# USB_Power.net
KiCad netlist of a schematic drawn in Altium Designer
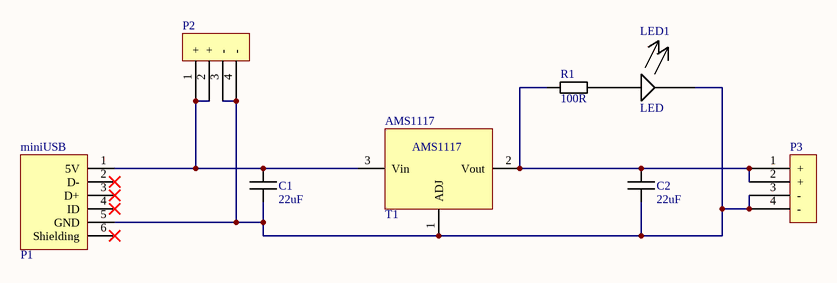
[diagram p0: USB Power.SchDoc]

(export (version "E")
  (design (tool "Eeschema 10.0.6"))
  (components
    (comp (ref "AMS1117")
      (value "T1")
      (footprint "SOT-223")
      (libsource (lib "AMS1117 breakout") (part "AMS1117"))
    )
    (comp (ref "C1")
      (value "22uF")
      (footprint "0805-C")
      (libsource (lib "AMS1117 breakout") (part "Capacitor"))
    )
    (comp (ref "C2")
      (value "22uF")
      (footprint "0805-C")
      (libsource (lib "AMS1117 breakout") (part "Capacitor"))
    )
    (comp (ref "LED1") (value "LED") (footprint "LED 3mm") (libsource (lib "LEDs") (part "LED")))
    (comp (ref "miniUSB")
      (value "P1")
      (footprint "miniUSB")
      (libsource (lib "AMS1117 breakout") (part "miniUSB"))
    )
    (comp (ref "P2")
      (value "Header 1x4 ++--")
      (footprint "Header 4x1 long")
      (libsource (lib "") (part "Header 1x4 ++--_1"))
    )
    (comp (ref "P3")
      (value "Header 1x4 ++--")
      (footprint "Header 4x1 long")
      (libsource (lib "Headers") (part "Header 1x4 ++--"))
    )
    (comp (ref "R1")
      (value "100R")
      (footprint "R 0805 / 2012")
      (libsource (lib "Standard") (part "Resistor"))
    )
  )
  (nets
    (net (code "1") (name "Net-(AMS1117-ADJ)") (class "Default")
      (node (ref "AMS1117") (pin "1") (pinfunction "ADJ_1") (pintype "passive"))
      (node (ref "C1") (pin "1") (pinfunction "1_1") (pintype "passive"))
      (node (ref "C2") (pin "1") (pinfunction "1_1") (pintype "passive"))
      (node (ref "LED1") (pin "2") (pinfunction "-_2") (pintype "passive"))
      (node (ref "P2") (pin "3") (pinfunction "-_3") (pintype "passive"))
      (node (ref "P2") (pin "4") (pinfunction "-_4") (pintype "passive"))
      (node (ref "P3") (pin "3") (pinfunction "-_3") (pintype "passive"))
      (node (ref "P3") (pin "4") (pinfunction "-_4") (pintype "passive"))
      (node (ref "miniUSB") (pin "5") (pinfunction "GND_5") (pintype "passive"))
    )
    (net (code "2") (name "Net-(AMS1117-Vin)") (class "Default")
      (node (ref "AMS1117") (pin "3") (pinfunction "Vin_3") (pintype "passive"))
      (node (ref "C1") (pin "2") (pinfunction "2_2") (pintype "passive"))
      (node (ref "P2") (pin "1") (pinfunction "+_1") (pintype "passive"))
      (node (ref "P2") (pin "2") (pinfunction "+_2") (pintype "passive"))
      (node (ref "miniUSB") (pin "1") (pinfunction "5V_1") (pintype "passive"))
    )
    (net (code "3") (name "Net-(AMS1117-Vout)") (class "Default")
      (node (ref "AMS1117") (pin "2") (pinfunction "Vout_2") (pintype "passive"))
      (node (ref "C2") (pin "2") (pinfunction "2_2") (pintype "passive"))
      (node (ref "P3") (pin "1") (pinfunction "+_1") (pintype "passive"))
      (node (ref "P3") (pin "2") (pinfunction "+_2") (pintype "passive"))
      (node (ref "R1") (pin "1") (pinfunction "1_1") (pintype "passive"))
    )
    (net (code "4") (name "Net-(LED1-+)") (class "Default")
      (node (ref "LED1") (pin "1") (pinfunction "+_1") (pintype "passive"))
      (node (ref "R1") (pin "2") (pinfunction "2_2") (pintype "passive"))
    )
    (net (code "5") (name "unconnected-(miniUSB-D+-Pad3)") (class "Default")
      (node (ref "miniUSB") (pin "3") (pinfunction "D+_3") (pintype "passive+no_connect"))
    )
    (net (code "6") (name "unconnected-(miniUSB-D--Pad2)") (class "Default")
      (node (ref "miniUSB") (pin "2") (pinfunction "D-_2") (pintype "passive+no_connect"))
    )
    (net (code "7") (name "unconnected-(miniUSB-ID-Pad4)") (class "Default")
      (node (ref "miniUSB") (pin "4") (pinfunction "ID_4") (pintype "passive+no_connect"))
    )
    (net (code "8") (name "unconnected-(miniUSB-Shielding-Pad6)") (class "Default")
      (node (ref "miniUSB") (pin "6") (pinfunction "Shielding_6") (pintype "passive+no_connect"))
    )
  )
)
